# V72_FPGA.net
KiCad netlist of a schematic drawn in Altium Designer
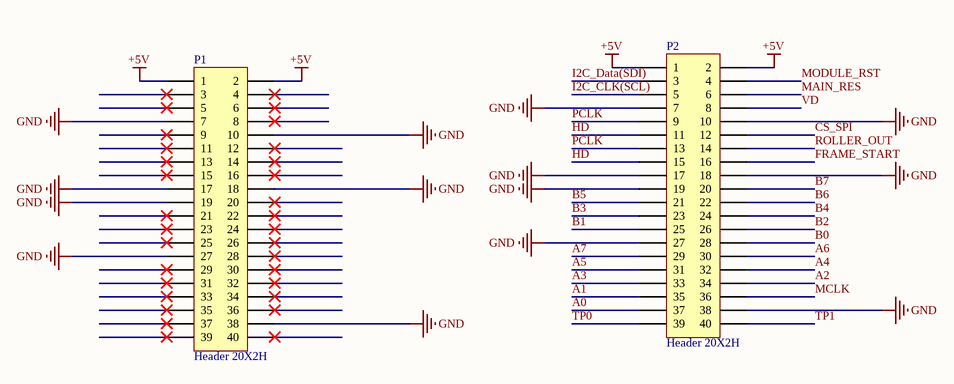
[diagram p0: V72_FPGA.SchDoc]

(export (version "E")
  (design (tool "Eeschema 10.0.6"))
  (components
    (comp (ref "P1")
      (value "Header 20X2H")
      (footprint "HDR2X20H")
      (description "Header, 20-Pin, Dual row, Right Angle")
      (fields (field (name "PUBLISHER") "Altium Limited"))
      (libsource (lib "Miscellaneous Connectors") (part "Header 20X2H"))
    )
    (comp (ref "P2")
      (value "Header 20X2H")
      (footprint "HDR2X20H")
      (description "Header, 20-Pin, Dual row, Right Angle")
      (fields (field (name "PUBLISHER") "Altium Limited"))
      (libsource (lib "Miscellaneous Connectors") (part "Header 20X2H"))
    )
  )
  (nets
    (net (code "1") (name "+5V") (class "Default")
      (node (ref "P1") (pin "1") (pinfunction "1_1") (pintype "passive"))
      (node (ref "P1") (pin "2") (pinfunction "2_2") (pintype "passive"))
      (node (ref "P2") (pin "1") (pinfunction "1_1") (pintype "passive"))
      (node (ref "P2") (pin "2") (pinfunction "2_2") (pintype "passive"))
    )
    (net (code "2") (name "/A0") (class "Default")
      (node (ref "P2") (pin "37") (pinfunction "37_37") (pintype "passive"))
    )
    (net (code "3") (name "/A1") (class "Default")
      (node (ref "P2") (pin "35") (pinfunction "35_35") (pintype "passive"))
    )
    (net (code "4") (name "/A2") (class "Default")
      (node (ref "P2") (pin "34") (pinfunction "34_34") (pintype "passive"))
    )
    (net (code "5") (name "/A3") (class "Default")
      (node (ref "P2") (pin "33") (pinfunction "33_33") (pintype "passive"))
    )
    (net (code "6") (name "/A4") (class "Default")
      (node (ref "P2") (pin "32") (pinfunction "32_32") (pintype "passive"))
    )
    (net (code "7") (name "/A5") (class "Default")
      (node (ref "P2") (pin "31") (pinfunction "31_31") (pintype "passive"))
    )
    (net (code "8") (name "/A6") (class "Default")
      (node (ref "P2") (pin "30") (pinfunction "30_30") (pintype "passive"))
    )
    (net (code "9") (name "/A7") (class "Default")
      (node (ref "P2") (pin "29") (pinfunction "29_29") (pintype "passive"))
    )
    (net (code "10") (name "/B0") (class "Default")
      (node (ref "P2") (pin "28") (pinfunction "28_28") (pintype "passive"))
    )
    (net (code "11") (name "/B1") (class "Default")
      (node (ref "P2") (pin "25") (pinfunction "25_25") (pintype "passive"))
    )
    (net (code "12") (name "/B2") (class "Default")
      (node (ref "P2") (pin "26") (pinfunction "26_26") (pintype "passive"))
    )
    (net (code "13") (name "/B3") (class "Default")
      (node (ref "P2") (pin "23") (pinfunction "23_23") (pintype "passive"))
    )
    (net (code "14") (name "/B4") (class "Default")
      (node (ref "P2") (pin "24") (pinfunction "24_24") (pintype "passive"))
    )
    (net (code "15") (name "/B5") (class "Default")
      (node (ref "P2") (pin "21") (pinfunction "21_21") (pintype "passive"))
    )
    (net (code "16") (name "/B6") (class "Default")
      (node (ref "P2") (pin "22") (pinfunction "22_22") (pintype "passive"))
    )
    (net (code "17") (name "/B7") (class "Default")
      (node (ref "P2") (pin "20") (pinfunction "20_20") (pintype "passive"))
    )
    (net (code "18") (name "/CS_SPI") (class "Default")
      (node (ref "P2") (pin "12") (pinfunction "12_12") (pintype "passive"))
    )
    (net (code "19") (name "/FRAME_START") (class "Default")
      (node (ref "P2") (pin "16") (pinfunction "16_16") (pintype "passive"))
    )
    (net (code "20") (name "/HD") (class "Default")
      (node (ref "P2") (pin "11") (pinfunction "11_11") (pintype "passive"))
      (node (ref "P2") (pin "15") (pinfunction "15_15") (pintype "passive"))
    )
    (net (code "21") (name "/I2C_CLK(SCL)") (class "Default")
      (node (ref "P2") (pin "5") (pinfunction "5_5") (pintype "passive"))
    )
    (net (code "22") (name "/I2C_Data(SDI)") (class "Default")
      (node (ref "P2") (pin "3") (pinfunction "3_3") (pintype "passive"))
    )
    (net (code "23") (name "/MAIN_RES") (class "Default")
      (node (ref "P2") (pin "6") (pinfunction "6_6") (pintype "passive"))
    )
    (net (code "24") (name "/MCLK") (class "Default")
      (node (ref "P2") (pin "36") (pinfunction "36_36") (pintype "passive"))
    )
    (net (code "25") (name "/MODULE_RST") (class "Default")
      (node (ref "P2") (pin "4") (pinfunction "4_4") (pintype "passive"))
    )
    (net (code "26") (name "/PCLK") (class "Default")
      (node (ref "P2") (pin "13") (pinfunction "13_13") (pintype "passive"))
      (node (ref "P2") (pin "9") (pinfunction "9_9") (pintype "passive"))
    )
    (net (code "27") (name "/ROLLER_OUT") (class "Default")
      (node (ref "P2") (pin "14") (pinfunction "14_14") (pintype "passive"))
    )
    (net (code "28") (name "/TP0") (class "Default")
      (node (ref "P2") (pin "39") (pinfunction "39_39") (pintype "passive"))
    )
    (net (code "29") (name "/TP1") (class "Default")
      (node (ref "P2") (pin "40") (pinfunction "40_40") (pintype "passive"))
    )
    (net (code "30") (name "/VD") (class "Default")
      (node (ref "P2") (pin "8") (pinfunction "8_8") (pintype "passive"))
    )
    (net (code "31") (name "GND") (class "Default")
      (node (ref "P1") (pin "10") (pinfunction "10_10") (pintype "passive"))
      (node (ref "P1") (pin "17") (pinfunction "17_17") (pintype "passive"))
      (node (ref "P1") (pin "18") (pinfunction "18_18") (pintype "passive"))
      (node (ref "P1") (pin "19") (pinfunction "19_19") (pintype "passive"))
      (node (ref "P1") (pin "27") (pinfunction "27_27") (pintype "passive"))
      (node (ref "P1") (pin "38") (pinfunction "38_38") (pintype "passive"))
      (node (ref "P1") (pin "7") (pinfunction "7_7") (pintype "passive"))
      (node (ref "P2") (pin "10") (pinfunction "10_10") (pintype "passive"))
      (node (ref "P2") (pin "17") (pinfunction "17_17") (pintype "passive"))
      (node (ref "P2") (pin "18") (pinfunction "18_18") (pintype "passive"))
      (node (ref "P2") (pin "19") (pinfunction "19_19") (pintype "passive"))
      (node (ref "P2") (pin "27") (pinfunction "27_27") (pintype "passive"))
      (node (ref "P2") (pin "38") (pinfunction "38_38") (pintype "passive"))
      (node (ref "P2") (pin "7") (pinfunction "7_7") (pintype "passive"))
    )
    (net (code "32") (name "unconnected-(P1-Pad3)") (class "Default")
      (node (ref "P1") (pin "3") (pinfunction "3_3") (pintype "passive+no_connect"))
    )
    (net (code "33") (name "unconnected-(P1-Pad4)") (class "Default")
      (node (ref "P1") (pin "4") (pinfunction "4_4") (pintype "passive+no_connect"))
    )
    (net (code "34") (name "unconnected-(P1-Pad5)") (class "Default")
      (node (ref "P1") (pin "5") (pinfunction "5_5") (pintype "passive+no_connect"))
    )
    (net (code "35") (name "unconnected-(P1-Pad6)") (class "Default")
      (node (ref "P1") (pin "6") (pinfunction "6_6") (pintype "passive+no_connect"))
    )
    (net (code "36") (name "unconnected-(P1-Pad8)") (class "Default")
      (node (ref "P1") (pin "8") (pinfunction "8_8") (pintype "passive+no_connect"))
    )
    (net (code "37") (name "unconnected-(P1-Pad9)") (class "Default")
      (node (ref "P1") (pin "9") (pinfunction "9_9") (pintype "passive+no_connect"))
    )
    (net (code "38") (name "unconnected-(P1-Pad11)") (class "Default")
      (node (ref "P1") (pin "11") (pinfunction "11_11") (pintype "passive+no_connect"))
    )
    (net (code "39") (name "unconnected-(P1-Pad12)") (class "Default")
      (node (ref "P1") (pin "12") (pinfunction "12_12") (pintype "passive+no_connect"))
    )
    (net (code "40") (name "unconnected-(P1-Pad13)") (class "Default")
      (node (ref "P1") (pin "13") (pinfunction "13_13") (pintype "passive+no_connect"))
    )
    (net (code "41") (name "unconnected-(P1-Pad14)") (class "Default")
      (node (ref "P1") (pin "14") (pinfunction "14_14") (pintype "passive+no_connect"))
    )
    (net (code "42") (name "unconnected-(P1-Pad15)") (class "Default")
      (node (ref "P1") (pin "15") (pinfunction "15_15") (pintype "passive+no_connect"))
    )
    (net (code "43") (name "unconnected-(P1-Pad16)") (class "Default")
      (node (ref "P1") (pin "16") (pinfunction "16_16") (pintype "passive+no_connect"))
    )
    (net (code "44") (name "unconnected-(P1-Pad20)") (class "Default")
      (node (ref "P1") (pin "20") (pinfunction "20_20") (pintype "passive+no_connect"))
    )
    (net (code "45") (name "unconnected-(P1-Pad21)") (class "Default")
      (node (ref "P1") (pin "21") (pinfunction "21_21") (pintype "passive+no_connect"))
    )
    (net (code "46") (name "unconnected-(P1-Pad22)") (class "Default")
      (node (ref "P1") (pin "22") (pinfunction "22_22") (pintype "passive+no_connect"))
    )
    (net (code "47") (name "unconnected-(P1-Pad23)") (class "Default")
      (node (ref "P1") (pin "23") (pinfunction "23_23") (pintype "passive+no_connect"))
    )
    (net (code "48") (name "unconnected-(P1-Pad24)") (class "Default")
      (node (ref "P1") (pin "24") (pinfunction "24_24") (pintype "passive+no_connect"))
    )
    (net (code "49") (name "unconnected-(P1-Pad25)") (class "Default")
      (node (ref "P1") (pin "25") (pinfunction "25_25") (pintype "passive+no_connect"))
    )
    (net (code "50") (name "unconnected-(P1-Pad26)") (class "Default")
      (node (ref "P1") (pin "26") (pinfunction "26_26") (pintype "passive+no_connect"))
    )
    (net (code "51") (name "unconnected-(P1-Pad28)") (class "Default")
      (node (ref "P1") (pin "28") (pinfunction "28_28") (pintype "passive+no_connect"))
    )
    (net (code "52") (name "unconnected-(P1-Pad29)") (class "Default")
      (node (ref "P1") (pin "29") (pinfunction "29_29") (pintype "passive+no_connect"))
    )
    (net (code "53") (name "unconnected-(P1-Pad30)") (class "Default")
      (node (ref "P1") (pin "30") (pinfunction "30_30") (pintype "passive+no_connect"))
    )
    (net (code "54") (name "unconnected-(P1-Pad31)") (class "Default")
      (node (ref "P1") (pin "31") (pinfunction "31_31") (pintype "passive+no_connect"))
    )
    (net (code "55") (name "unconnected-(P1-Pad32)") (class "Default")
      (node (ref "P1") (pin "32") (pinfunction "32_32") (pintype "passive+no_connect"))
    )
    (net (code "56") (name "unconnected-(P1-Pad33)") (class "Default")
      (node (ref "P1") (pin "33") (pinfunction "33_33") (pintype "passive+no_connect"))
    )
    (net (code "57") (name "unconnected-(P1-Pad34)") (class "Default")
      (node (ref "P1") (pin "34") (pinfunction "34_34") (pintype "passive+no_connect"))
    )
    (net (code "58") (name "unconnected-(P1-Pad35)") (class "Default")
      (node (ref "P1") (pin "35") (pinfunction "35_35") (pintype "passive+no_connect"))
    )
    (net (code "59") (name "unconnected-(P1-Pad36)") (class "Default")
      (node (ref "P1") (pin "36") (pinfunction "36_36") (pintype "passive+no_connect"))
    )
    (net (code "60") (name "unconnected-(P1-Pad37)") (class "Default")
      (node (ref "P1") (pin "37") (pinfunction "37_37") (pintype "passive+no_connect"))
    )
    (net (code "61") (name "unconnected-(P1-Pad39)") (class "Default")
      (node (ref "P1") (pin "39") (pinfunction "39_39") (pintype "passive+no_connect"))
    )
    (net (code "62") (name "unconnected-(P1-Pad40)") (class "Default")
      (node (ref "P1") (pin "40") (pinfunction "40_40") (pintype "passive+no_connect"))
    )
  )
)
